# GTU-2-V1_1-20160516.net
KiCad netlist of a schematic drawn in Altium Designer
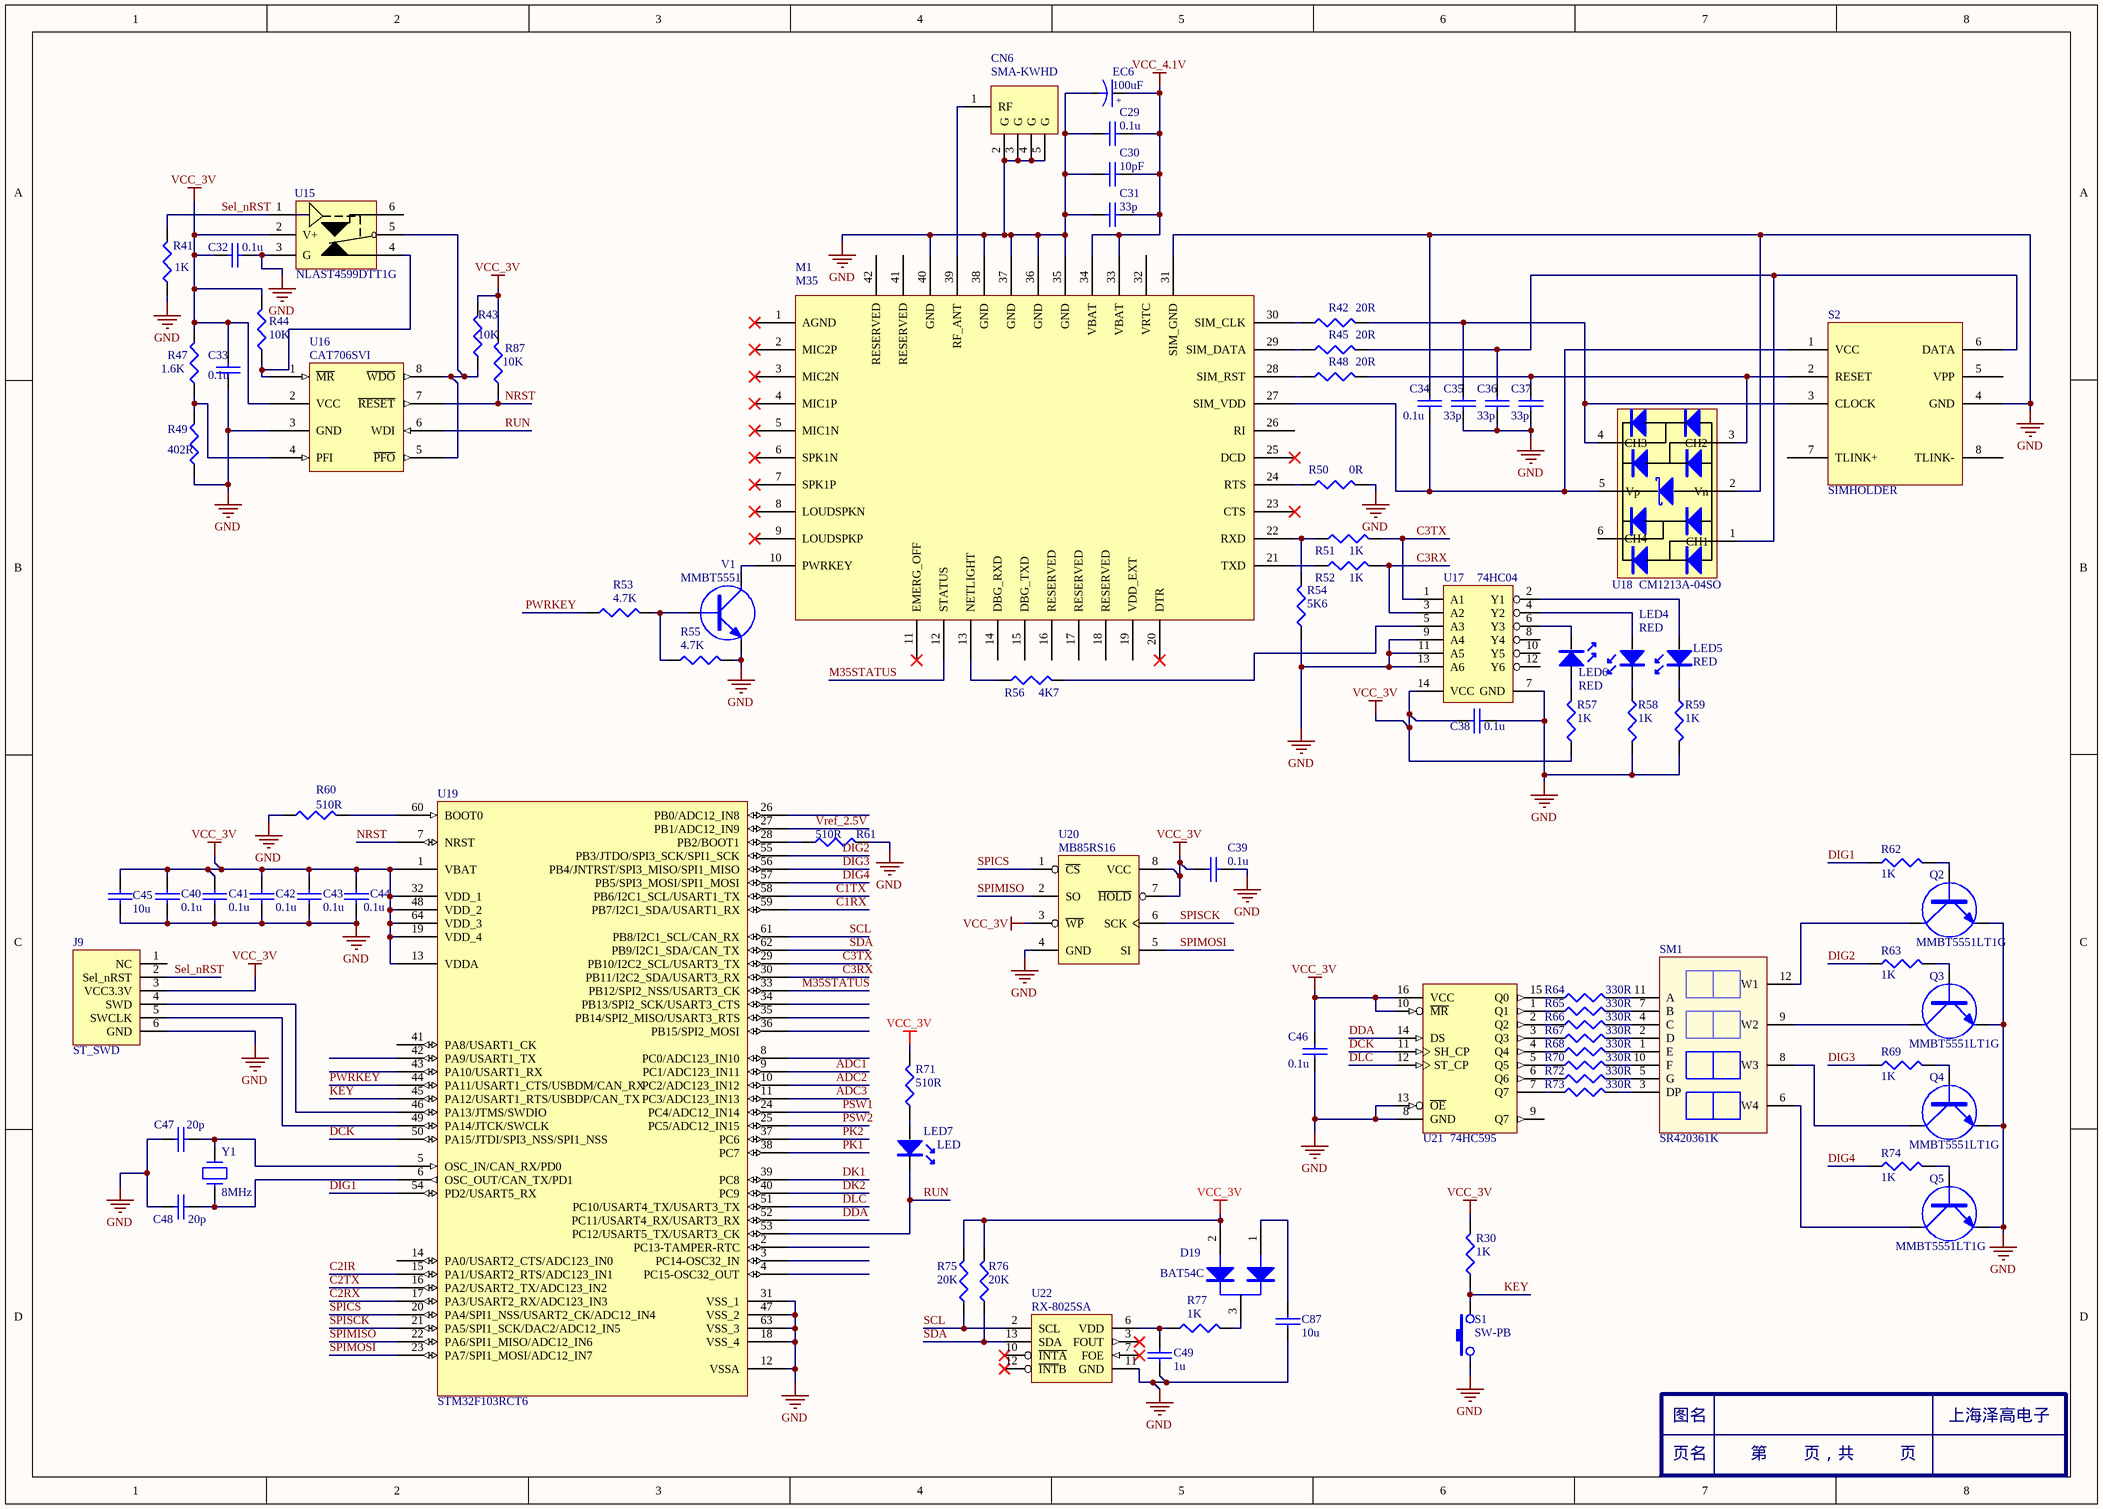
[diagram p0: GTU-2-V1.1-20160516.SCHDOC]

(export (version "E")
  (design (tool "Eeschema 10.0.6"))
  (components
    (comp (ref "4") (value "Component_1") (libsource (lib "*") (part "Component_1")))
    (comp (ref "C29")
      (value "0.1u")
      (footprint "0805-C")
      (description "Capacitor")
      (libsource (lib "STSCH-2014-01-20    ") (part "CAP"))
    )
    (comp (ref "C30")
      (value "10pF")
      (footprint "0805-C")
      (description "Capacitor")
      (libsource (lib "STSCH-2014-01-20    ") (part "CAP"))
    )
    (comp (ref "C31")
      (value "33p")
      (footprint "0805-C")
      (description "Capacitor")
      (libsource (lib "STSCH-2014-01-20    ") (part "CAP"))
    )
    (comp (ref "C32")
      (value "0.1u")
      (footprint "0805-C")
      (description "Capacitor")
      (fields (field (name "MFG") "TDK"))
      (libsource (lib "SCHLIB-ZG-2015.12.11      ") (part "CAP"))
    )
    (comp (ref "C33")
      (value "0.1u")
      (footprint "0805-C")
      (description "Capacitor")
      (libsource (lib "STSCH-2011-12-16") (part "CAP"))
    )
    (comp (ref "C34")
      (value "0.1u")
      (footprint "0805-C")
      (description "Capacitor")
      (libsource (lib "STSCH-2014-01-20    ") (part "CAP"))
    )
    (comp (ref "C35")
      (value "33p")
      (footprint "0805-C")
      (description "Capacitor")
      (libsource (lib "STSCH-2014-01-20    ") (part "CAP"))
    )
    (comp (ref "C36")
      (value "33p")
      (footprint "0805-C")
      (description "Capacitor")
      (libsource (lib "STSCH-2014-01-20    ") (part "CAP"))
    )
    (comp (ref "C37")
      (value "33p")
      (footprint "0805-C")
      (description "Capacitor")
      (libsource (lib "STSCH-2014-01-20    ") (part "CAP"))
    )
    (comp (ref "C38")
      (value "0.1u")
      (footprint "0805-C")
      (description "Capacitor")
      (libsource (lib "STSCH-2013-02-22   ") (part "CAP"))
    )
    (comp (ref "C39")
      (value "0.1u")
      (footprint "0805-C")
      (description "Capacitor")
      (libsource (lib "STSCH-2013-02-22   ") (part "CAP"))
    )
    (comp (ref "C40")
      (value "0.1u")
      (footprint "0805-C")
      (description "Capacitor")
      (libsource (lib "*") (part "CAP"))
    )
    (comp (ref "C41")
      (value "0.1u")
      (footprint "0805-C")
      (description "Capacitor")
      (libsource (lib "*") (part "CAP"))
    )
    (comp (ref "C42")
      (value "0.1u")
      (footprint "0805-C")
      (description "Capacitor")
      (libsource (lib "*") (part "CAP"))
    )
    (comp (ref "C43")
      (value "0.1u")
      (footprint "0805-C")
      (description "Capacitor")
      (libsource (lib "*") (part "CAP"))
    )
    (comp (ref "C44")
      (value "0.1u")
      (footprint "0805-C")
      (description "Capacitor")
      (libsource (lib "*") (part "CAP"))
    )
    (comp (ref "C45")
      (value "10u")
      (footprint "0805-C")
      (description "Capacitor")
      (libsource (lib "*") (part "CAP"))
    )
    (comp (ref "C46")
      (value "0.1u")
      (footprint "0805-C")
      (description "Capacitor")
      (libsource (lib "STSCH-2013-02-22   ") (part "CAP"))
    )
    (comp (ref "C47")
      (value "20p")
      (footprint "0805-C")
      (description "Capacitor")
      (libsource (lib "*") (part "CAP"))
    )
    (comp (ref "C48")
      (value "20p")
      (footprint "0805-C")
      (description "Capacitor")
      (libsource (lib "*") (part "CAP"))
    )
    (comp (ref "C49")
      (value "1u")
      (footprint "0805-C")
      (description "Capacitor")
      (libsource (lib "") (part "CAP_1"))
    )
    (comp (ref "C87")
      (value "10u")
      (footprint "0805-C")
      (description "Capacitor")
      (libsource (lib "") (part "CAP_1"))
    )
    (comp (ref "CN6")
      (value "SMA-KWHD")
      (footprint "SMA-KWHD")
      (description "RF插座")
      (libsource (lib "STSCH-2014-02-13    ") (part "SMA-KWHD"))
    )
    (comp (ref "D19") (value "BAT54C") (footprint "BAT54S/SOT-23") (libsource (lib "*") (part "BAT54C")))
    (comp (ref "EC6")
      (value "100uF")
      (footprint "7361-V")
      (libsource (lib "STSCH-2014-01-20    ") (part "CAP Tan"))
    )
    (comp (ref "J9")
      (value "ST_SWD")
      (footprint "SWD_DOWNLOAD")
      (description "STM32 SWD调试端口")
      (libsource (lib "SCHLIB-ZG-2015.12.11      ") (part "ST_SWD"))
    )
    (comp (ref "LED4")
      (value "RED")
      (footprint "0805-LED")
      (libsource (lib "STSCH-2012-11-26   ") (part "LED"))
    )
    (comp (ref "LED5")
      (value "RED")
      (footprint "0805-LED")
      (libsource (lib "STSCH-2012-11-26   ") (part "LED"))
    )
    (comp (ref "LED6")
      (value "RED")
      (footprint "0805-LED")
      (libsource (lib "STSCH-2012-11-26   ") (part "LED"))
    )
    (comp (ref "LED7") (value "LED") (footprint "0805-LED") (libsource (lib "STSCH-20110618") (part "LED")))
    (comp (ref "M1") (value "M35") (footprint "M35") (libsource (lib "STSCH-2014-01-20    ") (part "M35")))
    (comp (ref "Q2")
      (value "MMBT5551")
      (footprint "SOT-23")
      (description "NPN Transistor 160V 0.6A")
      (fields (field (name "MFG") "DIODES") (field (name "MFG2-PN") "MMBT5551LT1G"))
      (libsource (lib "SCHLIB-ZG-2016.01.18      ") (part "MMBT5551"))
    )
    (comp (ref "Q3")
      (value "MMBT5551")
      (footprint "SOT-23")
      (description "NPN Transistor 160V 0.6A")
      (fields (field (name "MFG") "DIODES") (field (name "MFG2-PN") "MMBT5551LT1G"))
      (libsource (lib "SCHLIB-ZG-2016.01.18      ") (part "MMBT5551"))
    )
    (comp (ref "Q4")
      (value "MMBT5551")
      (footprint "SOT-23")
      (description "NPN Transistor 160V 0.6A")
      (fields (field (name "MFG") "DIODES") (field (name "MFG2-PN") "MMBT5551LT1G"))
      (libsource (lib "SCHLIB-ZG-2016.01.18      ") (part "MMBT5551"))
    )
    (comp (ref "Q5")
      (value "MMBT5551")
      (footprint "SOT-23")
      (description "NPN Transistor 160V 0.6A")
      (fields (field (name "MFG") "DIODES") (field (name "MFG2-PN") "MMBT5551LT1G"))
      (libsource (lib "SCHLIB-ZG-2016.01.18      ") (part "MMBT5551"))
    )
    (comp (ref "R30") (value "1K") (footprint "0805-R") (libsource (lib "STSCH-2014-03-27    ") (part "RES")))
    (comp (ref "R41")
      (value "1K")
      (footprint "0805-R")
      (description "电阻")
      (fields (field (name "MFG") "YAGO") (field (name "Comment") "RES"))
      (libsource (lib "SCHLIB-ZG-2015.12.11      ") (part "RES"))
    )
    (comp (ref "R42")
      (value "20R")
      (footprint "0805-R")
      (libsource (lib "STSCH-2014-01-20    ") (part "RES"))
    )
    (comp (ref "R43") (value "10K") (footprint "0805-R") (libsource (lib "*") (part "RES")))
    (comp (ref "R44") (value "10K") (footprint "0805-R") (libsource (lib "*") (part "RES")))
    (comp (ref "R45")
      (value "20R")
      (footprint "0805-R")
      (libsource (lib "STSCH-2014-01-20    ") (part "RES"))
    )
    (comp (ref "R47")
      (value "1.6K")
      (footprint "0805-R")
      (description "电阻")
      (fields (field (name "MFG") "YAGO"))
      (libsource (lib "SCHLIB-ZG-2015.12.11      ") (part "RES"))
    )
    (comp (ref "R48")
      (value "20R")
      (footprint "0805-R")
      (libsource (lib "STSCH-2014-01-20    ") (part "RES"))
    )
    (comp (ref "R49")
      (value "402R")
      (footprint "0805-R")
      (description "电阻")
      (fields (field (name "MFG") "YAGO"))
      (libsource (lib "SCHLIB-ZG-2015.12.11      ") (part "RES"))
    )
    (comp (ref "R50") (value "0R") (footprint "0805-R") (libsource (lib "STSCH-2014-01-20    ") (part "RES")))
    (comp (ref "R51") (value "1K") (footprint "0805-R") (libsource (lib "STSCH-2014-01-20    ") (part "RES")))
    (comp (ref "R52") (value "1K") (footprint "0805-R") (libsource (lib "STSCH-2014-01-20    ") (part "RES")))
    (comp (ref "R53")
      (value "4.7K")
      (footprint "0805-R")
      (libsource (lib "STSCH-2014-01-20    ") (part "RES"))
    )
    (comp (ref "R54")
      (value "5K6")
      (footprint "0805-R")
      (libsource (lib "STSCH-2014-01-20    ") (part "RES"))
    )
    (comp (ref "R55")
      (value "4.7K")
      (footprint "0805-R")
      (libsource (lib "STSCH-2014-01-20    ") (part "RES"))
    )
    (comp (ref "R56")
      (value "4K7")
      (footprint "0805-R")
      (libsource (lib "STSCH-2014-02-12    ") (part "RES"))
    )
    (comp (ref "R57") (value "1K") (footprint "0805-R") (libsource (lib "STSCH-2012-11-26   ") (part "RES")))
    (comp (ref "R58") (value "1K") (footprint "0805-R") (libsource (lib "STSCH-2012-11-26   ") (part "RES")))
    (comp (ref "R59") (value "1K") (footprint "0805-R") (libsource (lib "STSCH-2012-11-26   ") (part "RES")))
    (comp (ref "R60") (value "510R") (footprint "0805-R") (libsource (lib "*") (part "RES")))
    (comp (ref "R61") (value "510R") (footprint "0805-R") (libsource (lib "*") (part "RES")))
    (comp (ref "R62")
      (value "1K")
      (footprint "0805-R")
      (description "电阻")
      (fields (field (name "MFG") "YAGO") (field (name "Comment") "RES"))
      (libsource (lib "SCHLIB-ZG-2016.01.18      ") (part "RES"))
    )
    (comp (ref "R63")
      (value "1K")
      (footprint "0805-R")
      (description "电阻")
      (fields (field (name "MFG") "YAGO") (field (name "Comment") "RES"))
      (libsource (lib "SCHLIB-ZG-2016.01.18      ") (part "RES"))
    )
    (comp (ref "R64") (value "330R") (footprint "0805-R") (libsource (lib "") (part "RES_1")))
    (comp (ref "R65") (value "330R") (footprint "0805-R") (libsource (lib "") (part "RES_1")))
    (comp (ref "R66") (value "330R") (footprint "0805-R") (libsource (lib "") (part "RES_1")))
    (comp (ref "R67") (value "330R") (footprint "0805-R") (libsource (lib "") (part "RES_1")))
    (comp (ref "R68") (value "330R") (footprint "0805-R") (libsource (lib "") (part "RES_1")))
    (comp (ref "R69")
      (value "1K")
      (footprint "0805-R")
      (description "电阻")
      (fields (field (name "MFG") "YAGO") (field (name "Comment") "RES"))
      (libsource (lib "SCHLIB-ZG-2016.01.18      ") (part "RES"))
    )
    (comp (ref "R70") (value "330R") (footprint "0805-R") (libsource (lib "") (part "RES_1")))
    (comp (ref "R71") (value "510R") (footprint "0805-R") (libsource (lib "STSCH-20110618") (part "RES")))
    (comp (ref "R72") (value "330R") (footprint "0805-R") (libsource (lib "") (part "RES_1")))
    (comp (ref "R73") (value "330R") (footprint "0805-R") (libsource (lib "") (part "RES_1")))
    (comp (ref "R74")
      (value "1K")
      (footprint "0805-R")
      (description "电阻")
      (fields (field (name "MFG") "YAGO") (field (name "Comment") "RES"))
      (libsource (lib "SCHLIB-ZG-2016.01.18      ") (part "RES"))
    )
    (comp (ref "R75") (value "20K") (footprint "0805-R") (libsource (lib "") (part "RES_1")))
    (comp (ref "R76") (value "20K") (footprint "0805-R") (libsource (lib "") (part "RES_1")))
    (comp (ref "R77") (value "1K") (footprint "0805-R") (libsource (lib "STSCH-2013-08-08    ") (part "RES")))
    (comp (ref "R87") (value "10K") (footprint "0805-R") (libsource (lib "*") (part "RES")))
    (comp (ref "S1")
      (value "SW-PB")
      (footprint "JMP")
      (description "轻触按钮")
      (libsource (lib "STSCH-2014-03-27    ") (part "SW-PB"))
    )
    (comp (ref "S2")
      (value "SIMHOLDER")
      (footprint "SIM-HOLDER")
      (libsource (lib "STSCH-2014-01-20    ") (part "SIMHOLDER"))
    )
    (comp (ref "SM1")
      (value "SR420361K")
      (footprint "SR420361")
      (description "共阴极0.28寸4位数码管品牌ARK")
      (libsource (lib "SCHLIB-ZG-2016.01.18      ") (part "SR420361"))
    )
    (comp (ref "U15")
      (value "NLAST4599DTT1G")
      (footprint "SOT-23-6")
      (libsource (lib "轨旁检测-20151210") (part "NLAST4599DTT1G"))
    )
    (comp (ref "U16") (value "CAT706SVI") (footprint "SO-8") (libsource (lib "*") (part "SP706T")))
    (comp (ref "U17")
      (value "74HC04")
      (footprint "SO-14")
      (libsource (lib "STSCH-2014-05-18     ") (part "74HC04"))
    )
    (comp (ref "U18")
      (value "CM1213A-04SO")
      (footprint "SOT-23-6")
      (libsource (lib "STSCH-2015.09.30  ") (part "CM1213A-04SO"))
    )
    (comp (ref "U19")
      (value "STM32F103RCT6")
      (footprint "LQFP-64")
      (libsource (lib "STSCH-2014-01-15") (part "STM32F103RCT6"))
    )
    (comp (ref "U20")
      (value "MB85RS16")
      (footprint "SO-8")
      (libsource (lib "STSCH-2013-02-22   ") (part "FM25256B"))
    )
    (comp (ref "U21")
      (value "74HC595")
      (footprint "SO-16")
      (description "8位移位寄存器")
      (fields (field (name "MFG") "NXP"))
      (libsource (lib "SCHLIB-ZG-2016.01.18      ") (part "74HC595"))
    )
    (comp (ref "U22") (value "RX-8025SA") (footprint "SO-14") (libsource (lib "*") (part "RX-8025SA")))
    (comp (ref "V1")
      (value "MMBT5551")
      (footprint "SOT-23")
      (description "贴片NPN")
      (libsource (lib "STSCH-2014-01-20    ") (part "MMBT5551"))
    )
    (comp (ref "Y1")
      (value "8MHz")
      (footprint "SM-49")
      (description "Crystal")
      (libsource (lib "*") (part "CRYSTAL"))
    )
  )
  (nets
    (net (code "1") (name "/ADC1") (class "Default")
      (node (ref "U19") (pin "9") (pinfunction "PC1/ADC123_IN11_9") (pintype "bidirectional"))
    )
    (net (code "2") (name "/ADC2") (class "Default")
      (node (ref "U19") (pin "10") (pinfunction "PC2/ADC123_IN12_10") (pintype "bidirectional"))
    )
    (net (code "3") (name "/ADC3") (class "Default")
      (node (ref "U19") (pin "11") (pinfunction "PC3/ADC123_IN13_11") (pintype "bidirectional"))
    )
    (net (code "4") (name "/C1RX") (class "Default")
      (node (ref "U19") (pin "59") (pinfunction "PB7/I2C1_SDA/USART1_RX_59") (pintype "bidirectional"))
    )
    (net (code "5") (name "/C1TX") (class "Default")
      (node (ref "U19") (pin "58") (pinfunction "PB6/I2C1_SCL/USART1_TX_58") (pintype "bidirectional"))
    )
    (net (code "6") (name "/C2IR") (class "Default")
      (node (ref "U19") (pin "15") (pinfunction "PA1/USART2_RTS/ADC123_IN1_15") (pintype "bidirectional"))
    )
    (net (code "7") (name "/C2RX") (class "Default")
      (node (ref "U19") (pin "17") (pinfunction "PA3/USART2_RX/ADC123_IN3_17") (pintype "bidirectional"))
    )
    (net (code "8") (name "/C2TX") (class "Default")
      (node (ref "U19") (pin "16") (pinfunction "PA2/USART2_TX/ADC123_IN2_16") (pintype "bidirectional"))
    )
    (net (code "9") (name "/C3RX") (class "Default")
      (node (ref "R52") (pin "2") (pinfunction "2_2") (pintype "passive"))
      (node (ref "U17") (pin "3") (pinfunction "A2_3") (pintype "passive"))
      (node (ref "U19") (pin "30") (pinfunction "PB11/I2C2_SDA/USART3_RX_30") (pintype "bidirectional"))
    )
    (net (code "10") (name "/C3TX") (class "Default")
      (node (ref "R51") (pin "2") (pinfunction "2_2") (pintype "passive"))
      (node (ref "U17") (pin "1") (pinfunction "A1_1") (pintype "passive"))
      (node (ref "U19") (pin "29") (pinfunction "PB10/I2C2_SCL/USART3_TX_29") (pintype "bidirectional"))
    )
    (net (code "11") (name "/DCK") (class "Default")
      (node (ref "U19") (pin "50") (pinfunction "PA15/JTDI/SPI3_NSS/SPI1_NSS_50") (pintype "bidirectional"))
      (node (ref "U21") (pin "11") (pinfunction "SH_CP_11") (pintype "input"))
    )
    (net (code "12") (name "/DDA") (class "Default")
      (node (ref "U19") (pin "52") (pinfunction "PC11/USART4_RX/USART3_RX_52") (pintype "bidirectional"))
      (node (ref "U21") (pin "14") (pinfunction "DS_14") (pintype "input"))
    )
    (net (code "13") (name "/DIG1") (class "Default")
      (node (ref "R62") (pin "1") (pinfunction "1_1") (pintype "passive"))
      (node (ref "U19") (pin "54") (pinfunction "PD2/USART5_RX_54") (pintype "bidirectional"))
    )
    (net (code "14") (name "/DIG2") (class "Default")
      (node (ref "R63") (pin "1") (pinfunction "1_1") (pintype "passive"))
      (node (ref "U19") (pin "55") (pinfunction "PB3/JTDO/SPI3_SCK/SPI1_SCK_55") (pintype "bidirectional"))
    )
    (net (code "15") (name "/DIG3") (class "Default")
      (node (ref "R69") (pin "1") (pinfunction "1_1") (pintype "passive"))
      (node (ref "U19") (pin "56") (pinfunction "PB4/JNTRST/SPI3_MISO/SPI1_MISO_56") (pintype "bidirectional"))
    )
    (net (code "16") (name "/DIG4") (class "Default")
      (node (ref "R74") (pin "1") (pinfunction "1_1") (pintype "passive"))
      (node (ref "U19") (pin "57") (pinfunction "PB5/SPI3_MOSI/SPI1_MOSI_57") (pintype "bidirectional"))
    )
    (net (code "17") (name "/DK1") (class "Default")
      (node (ref "U19") (pin "39") (pinfunction "PC8_39") (pintype "bidirectional"))
    )
    (net (code "18") (name "/DK2") (class "Default")
      (node (ref "U19") (pin "40") (pinfunction "PC9_40") (pintype "bidirectional"))
    )
    (net (code "19") (name "/DLC") (class "Default")
      (node (ref "U19") (pin "51") (pinfunction "PC10/USART4_TX/USART3_TX_51") (pintype "bidirectional"))
      (node (ref "U21") (pin "12") (pinfunction "ST_CP_12") (pintype "input"))
    )
    (net (code "20") (name "/KEY") (class "Default")
      (node (ref "R30") (pin "1") (pinfunction "1_1") (pintype "passive"))
      (node (ref "S1") (pin "2") (pinfunction "2_2") (pintype "passive"))
      (node (ref "U19") (pin "45") (pinfunction "PA12/USART1_RTS/USBDP/CAN_TX_45") (pintype "bidirectional"))
    )
    (net (code "21") (name "/M35STATUS") (class "Default")
      (node (ref "M1") (pin "12") (pinfunction "STATUS_12") (pintype "passive"))
      (node (ref "U19") (pin "33") (pinfunction "PB12/SPI2_NSS/USART3_CK_33") (pintype "bidirectional"))
    )
    (net (code "22") (name "/NRST") (class "Default")
      (node (ref "R87") (pin "1") (pinfunction "1_1") (pintype "passive"))
      (node (ref "U16") (pin "7") (pinfunction "~{RESET}_7") (pintype "output"))
      (node (ref "U19") (pin "7") (pinfunction "NRST_7") (pintype "bidirectional"))
    )
    (net (code "23") (name "/PK1") (class "Default")
      (node (ref "U19") (pin "38") (pinfunction "PC7_38") (pintype "bidirectional"))
    )
    (net (code "24") (name "/PK2") (class "Default")
      (node (ref "U19") (pin "37") (pinfunction "PC6_37") (pintype "bidirectional"))
    )
    (net (code "25") (name "/PSW1") (class "Default")
      (node (ref "U19") (pin "24") (pinfunction "PC4/ADC12_IN14_24") (pintype "bidirectional"))
    )
    (net (code "26") (name "/PSW2") (class "Default")
      (node (ref "U19") (pin "25") (pinfunction "PC5/ADC12_IN15_25") (pintype "bidirectional"))
    )
    (net (code "27") (name "/PWRKEY") (class "Default")
      (node (ref "R53") (pin "1") (pinfunction "1_1") (pintype "passive"))
      (node (ref "U19") (pin "44") (pinfunction "PA11/USART1_CTS/USBDM/CAN_RX_44") (pintype "bidirectional"))
    )
    (net (code "28") (name "/RUN") (class "Default")
      (node (ref "LED7") (pin "2") (pintype "passive"))
      (node (ref "U16") (pin "6") (pinfunction "WDI_6") (pintype "input"))
      (node (ref "U19") (pin "53") (pinfunction "PC12/USART5_TX/USART3_CK_53") (pintype "bidirectional"))
    )
    (net (code "29") (name "/SCL") (class "Default")
      (node (ref "R75") (pin "1") (pinfunction "1_1") (pintype "passive"))
      (node (ref "U19") (pin "61") (pinfunction "PB8/I2C1_SCL/CAN_RX_61") (pintype "bidirectional"))
      (node (ref "U22") (pin "2") (pinfunction "SCL_2") (pintype "open_collector"))
    )
    (net (code "30") (name "/SDA") (class "Default")
      (node (ref "R76") (pin "1") (pinfunction "1_1") (pintype "passive"))
      (node (ref "U19") (pin "62") (pinfunction "PB9/I2C1_SDA/CAN_TX_62") (pintype "bidirectional"))
      (node (ref "U22") (pin "13") (pinfunction "SDA_13") (pintype "passive"))
    )
    (net (code "31") (name "/SPICS") (class "Default")
      (node (ref "U19") (pin "20") (pinfunction "PA4/SPI1_NSS/USART2_CK/ADC12_IN4_20") (pintype "bidirectional"))
      (node (ref "U20") (pin "1") (pinfunction "~{CS}_1") (pintype "passive"))
    )
    (net (code "32") (name "/SPIMISO") (class "Default")
      (node (ref "U19") (pin "22") (pinfunction "PA6/SPI1_MISO/ADC12_IN6_22") (pintype "bidirectional"))
      (node (ref "U20") (pin "2") (pinfunction "SO_2") (pintype "passive"))
    )
    (net (code "33") (name "/SPIMOSI") (class "Default")
      (node (ref "U19") (pin "23") (pinfunction "PA7/SPI1_MOSI/ADC12_IN7_23") (pintype "bidirectional"))
      (node (ref "U20") (pin "5") (pinfunction "SI_5") (pintype "passive"))
    )
    (net (code "34") (name "/SPISCK") (class "Default")
      (node (ref "U19") (pin "21") (pinfunction "PA5/SPI1_SCK/DAC2/ADC12_IN5_21") (pintype "bidirectional"))
      (node (ref "U20") (pin "6") (pinfunction "SCK_6") (pintype "passive"))
    )
    (net (code "35") (name "/Sel_nRST") (class "Default")
      (node (ref "J9") (pin "2") (pinfunction "Sel_nRST_2") (pintype "passive"))
      (node (ref "R41") (pin "2") (pinfunction "2_2") (pintype "passive"))
      (node (ref "U15") (pin "1") (pinfunction "SELECT_1") (pintype "passive"))
    )
    (net (code "36") (name "/Vref_2.5V") (class "Default")
      (node (ref "U19") (pin "27") (pinfunction "PB1/ADC12_IN9_27") (pintype "bidirectional"))
    )
    (net (code "37") (name "GND") (class "Default")
      (node (ref "C29") (pin "2") (pinfunction "2_2") (pintype "passive"))
      (node (ref "C30") (pin "2") (pinfunction "2_2") (pintype "passive"))
      (node (ref "C31") (pin "2") (pinfunction "2_2") (pintype "passive"))
      (node (ref "C32") (pin "2") (pinfunction "2_2") (pintype "passive"))
      (node (ref "C33") (pin "2") (pinfunction "2_2") (pintype "passive"))
      (node (ref "C34") (pin "1") (pinfunction "1_1") (pintype "passive"))
      (node (ref "C35") (pin "2") (pinfunction "2_2") (pintype "passive"))
      (node (ref "C36") (pin "2") (pinfunction "2_2") (pintype "passive"))
      (node (ref "C37") (pin "2") (pinfunction "2_2") (pintype "passive"))
      (node (ref "C38") (pin "2") (pinfunction "2_2") (pintype "passive"))
      (node (ref "C39") (pin "2") (pinfunction "2_2") (pintype "passive"))
      (node (ref "C40") (pin "2") (pinfunction "2_2") (pintype "passive"))
      (node (ref "C41") (pin "2") (pinfunction "2_2") (pintype "passive"))
      (node (ref "C42") (pin "2") (pinfunction "2_2") (pintype "passive"))
      (node (ref "C43") (pin "2") (pinfunction "2_2") (pintype "passive"))
      (node (ref "C44") (pin "2") (pinfunction "2_2") (pintype "passive"))
      (node (ref "C45") (pin "2") (pinfunction "2_2") (pintype "passive"))
      (node (ref "C46") (pin "2") (pinfunction "2_2") (pintype "passive"))
      (node (ref "C47") (pin "2") (pinfunction "2_2") (pintype "passive"))
      (node (ref "C48") (pin "2") (pinfunction "2_2") (pintype "passive"))
      (node (ref "C49") (pin "2") (pinfunction "2_2") (pintype "passive"))
      (node (ref "C87") (pin "2") (pinfunction "2_2") (pintype "passive"))
      (node (ref "CN6") (pin "2") (pinfunction "G_2") (pintype "passive"))
      (node (ref "CN6") (pin "3") (pinfunction "G_3") (pintype "passive"))
      (node (ref "CN6") (pin "4") (pinfunction "G_4") (pintype "passive"))
      (node (ref "CN6") (pin "5") (pinfunction "G_5") (pintype "passive"))
      (node (ref "EC6") (pin "2") (pinfunction "2_2") (pintype "passive"))
      (node (ref "J9") (pin "6") (pinfunction "GND_6") (pintype "passive"))
      (node (ref "M1") (pin "31") (pinfunction "SIM_GND_31") (pintype "passive"))
      (node (ref "M1") (pin "35") (pinfunction "GND_35") (pintype "passive"))
      (node (ref "M1") (pin "36") (pinfunction "GND_36") (pintype "passive"))
      (node (ref "M1") (pin "37") (pinfunction "GND_37") (pintype "passive"))
      (node (ref "M1") (pin "38") (pinfunction "GND_38") (pintype "passive"))
      (node (ref "M1") (pin "40") (pinfunction "GND_40") (pintype "passive"))
      (node (ref "Q2") (pin "2") (pinfunction "E_2") (pintype "passive"))
      (node (ref "Q3") (pin "2") (pinfunction "E_2") (pintype "passive"))
      (node (ref "Q4") (pin "2") (pinfunction "E_2") (pintype "passive"))
      (node (ref "Q5") (pin "2") (pinfunction "E_2") (pintype "passive"))
      (node (ref "R41") (pin "1") (pinfunction "1_1") (pintype "passive"))
      (node (ref "R49") (pin "1") (pinfunction "1_1") (pintype "passive"))
      (node (ref "R50") (pin "2") (pinfunction "2_2") (pintype "passive"))
      (node (ref "R54") (pin "1") (pinfunction "1_1") (pintype "passive"))
      (node (ref "R55") (pin "2") (pinfunction "2_2") (pintype "passive"))
      (node (ref "R58") (pin "2") (pinfunction "2_2") (pintype "passive"))
      (node (ref "R59") (pin "2") (pinfunction "2_2") (pintype "passive"))
      (node (ref "R60") (pin "1") (pinfunction "1_1") (pintype "passive"))
      (node (ref "R61") (pin "2") (pinfunction "2_2") (pintype "passive"))
      (node (ref "S1") (pin "1") (pinfunction "1_1") (pintype "passive"))
      (node (ref "S2") (pin "4") (pinfunction "GND_4") (pintype "passive"))
      (node (ref "U15") (pin "3") (pinfunction "G_3") (pintype "passive"))
      (node (ref "U16") (pin "3") (pinfunction "GND_3") (pintype "power_in"))
      (node (ref "U17") (pin "11") (pinfunction "A5_11") (pintype "passive"))
      (node (ref "U17") (pin "13") (pinfunction "A6_13") (pintype "passive"))
      (node (ref "U17") (pin "7") (pinfunction "GND_7") (pintype "passive"))
      (node (ref "U17") (pin "9") (pinfunction "A4_9") (pintype "passive"))
      (node (ref "U18") (pin "2") (pinfunction "Vn_2") (pintype "passive"))
      (node (ref "U19") (pin "12") (pinfunction "VSSA_12") (pintype "power_in"))
      (node (ref "U19") (pin "18") (pinfunction "VSS_4_18") (pintype "power_in"))
      (node (ref "U19") (pin "31") (pinfunction "VSS_1_31") (pintype "power_in"))
      (node (ref "U19") (pin "47") (pinfunction "VSS_2_47") (pintype "power_in"))
      (node (ref "U19") (pin "63") (pinfunction "VSS_3_63") (pintype "power_in"))
      (node (ref "U20") (pin "4") (pinfunction "GND_4") (pintype "passive"))
      (node (ref "U21") (pin "13") (pinfunction "~{OE}_13") (pintype "input"))
      (node (ref "U21") (pin "8") (pinfunction "GND_8") (pintype "power_in"))
      (node (ref "U22") (pin "11") (pinfunction "GND_11") (pintype "power_in"))
      (node (ref "V1") (pin "2") (pinfunction "E_2") (pintype "passive"))
    )
    (net (code "38") (name "Net-(C87-Pad1)") (class "Default")
      (node (ref "C87") (pin "1") (pinfunction "1_1") (pintype "passive"))
      (node (ref "D19") (pin "1") (pintype "passive"))
    )
    (net (code "39") (name "Net-(CN6-RF)") (class "Default")
      (node (ref "CN6") (pin "1") (pinfunction "RF_1") (pintype "passive"))
      (node (ref "M1") (pin "39") (pinfunction "RF_ANT_39") (pintype "passive"))
    )
    (net (code "40") (name "Net-(D19-Pad3)") (class "Default")
      (node (ref "D19") (pin "3") (pintype "passive"))
      (node (ref "R77") (pin "2") (pinfunction "2_2") (pintype "passive"))
    )
    (net (code "41") (name "Net-(J9-SWCLK)") (class "Default")
      (node (ref "J9") (pin "5") (pinfunction "SWCLK_5") (pintype "passive"))
      (node (ref "U19") (pin "49") (pinfunction "PA14/JTCK/SWCLK_49") (pintype "bidirectional"))
    )
    (net (code "42") (name "Net-(J9-SWD)") (class "Default")
      (node (ref "J9") (pin "4") (pinfunction "SWD_4") (pintype "passive"))
      (node (ref "U19") (pin "46") (pinfunction "PA13/JTMS/SWDIO_46") (pintype "bidirectional"))
    )
    (net (code "43") (name "Net-(LED4-Pad2)") (class "Default")
      (node (ref "LED4") (pin "2") (pintype "passive"))
      (node (ref "R58") (pin "1") (pinfunction "1_1") (pintype "passive"))
    )
    (net (code "44") (name "Net-(LED5-Pad2)") (class "Default")
      (node (ref "LED5") (pin "2") (pintype "passive"))
      (node (ref "R59") (pin "1") (pinfunction "1_1") (pintype "passive"))
    )
    (net (code "45") (name "Net-(LED6-Pad1)") (class "Default")
      (node (ref "LED6") (pin "1") (pintype "passive"))
      (node (ref "R57") (pin "2") (pinfunction "2_2") (pintype "passive"))
    )
    (net (code "46") (name "Net-(LED7-Pad1)") (class "Default")
      (node (ref "LED7") (pin "1") (pintype "passive"))
      (node (ref "R71") (pin "1") (pinfunction "1_1") (pintype "passive"))
    )
    (net (code "47") (name "Net-(M1-NETLIGHT)") (class "Default")
      (node (ref "M1") (pin "13") (pinfunction "NETLIGHT_13") (pintype "passive"))
      (node (ref "R56") (pin "1") (pinfunction "1_1") (pintype "passive"))
    )
    (net (code "48") (name "Net-(M1-PWRKEY)") (class "Default")
      (node (ref "M1") (pin "10") (pinfunction "PWRKEY_10") (pintype "passive"))
      (node (ref "V1") (pin "3") (pinfunction "C_3") (pintype "passive"))
    )
    (net (code "49") (name "Net-(M1-RTS)") (class "Default")
      (node (ref "M1") (pin "24") (pinfunction "RTS_24") (pintype "passive"))
      (node (ref "R50") (pin "1") (pinfunction "1_1") (pintype "passive"))
    )
    (net (code "50") (name "Net-(M1-RXD)") (class "Default")
      (node (ref "M1") (pin "22") (pinfunction "RXD_22") (pintype "passive"))
      (node (ref "R51") (pin "1") (pinfunction "1_1") (pintype "passive"))
      (node (ref "R54") (pin "2") (pinfunction "2_2") (pintype "passive"))
    )
    (net (code "51") (name "Net-(M1-SIM_CLK)") (class "Default")
      (node (ref "M1") (pin "30") (pinfunction "SIM_CLK_30") (pintype "passive"))
      (node (ref "R42") (pin "1") (pinfunction "1_1") (pintype "passive"))
    )
    (net (code "52") (name "Net-(M1-SIM_DATA)") (class "Default")
      (node (ref "M1") (pin "29") (pinfunction "SIM_DATA_29") (pintype "passive"))
      (node (ref "R45") (pin "1") (pinfunction "1_1") (pintype "passive"))
    )
    (net (code "53") (name "Net-(M1-SIM_RST)") (class "Default")
      (node (ref "M1") (pin "28") (pinfunction "SIM_RST_28") (pintype "passive"))
      (node (ref "R48") (pin "1") (pinfunction "1_1") (pintype "passive"))
    )
    (net (code "54") (name "Net-(M1-SIM_VDD)") (class "Default")
      (node (ref "C34") (pin "2") (pinfunction "2_2") (pintype "passive"))
      (node (ref "M1") (pin "27") (pinfunction "SIM_VDD_27") (pintype "passive"))
      (node (ref "S2") (pin "1") (pinfunction "VCC_1") (pintype "passive"))
      (node (ref "U18") (pin "5") (pinfunction "Vp_5") (pintype "passive"))
    )
    (net (code "55") (name "Net-(M1-TXD)") (class "Default")
      (node (ref "M1") (pin "21") (pinfunction "TXD_21") (pintype "passive"))
      (node (ref "R52") (pin "1") (pinfunction "1_1") (pintype "passive"))
    )
    (net (code "56") (name "Net-(Q2-B)") (class "Default")
      (node (ref "Q2") (pin "1") (pinfunction "B_1") (pintype "passive"))
      (node (ref "R62") (pin "2") (pinfunction "2_2") (pintype "passive"))
    )
    (net (code "57") (name "Net-(Q2-C)") (class "Default")
      (node (ref "Q2") (pin "3") (pinfunction "C_3") (pintype "passive"))
      (node (ref "SM1") (pin "12") (pinfunction "W1_12") (pintype "passive"))
    )
    (net (code "58") (name "Net-(Q3-B)") (class "Default")
      (node (ref "Q3") (pin "1") (pinfunction "B_1") (pintype "passive"))
      (node (ref "R63") (pin "2") (pinfunction "2_2") (pintype "passive"))
    )
    (net (code "59") (name "Net-(Q3-C)") (class "Default")
      (node (ref "Q3") (pin "3") (pinfunction "C_3") (pintype "passive"))
      (node (ref "SM1") (pin "9") (pinfunction "W2_9") (pintype "passive"))
    )
    (net (code "60") (name "Net-(Q4-B)") (class "Default")
      (node (ref "Q4") (pin "1") (pinfunction "B_1") (pintype "passive"))
      (node (ref "R69") (pin "2") (pinfunction "2_2") (pintype "passive"))
    )
    (net (code "61") (name "Net-(Q4-C)") (class "Default")
      (node (ref "Q4") (pin "3") (pinfunction "C_3") (pintype "passive"))
      (node (ref "SM1") (pin "8") (pinfunction "W3_8") (pintype "passive"))
    )
    (net (code "62") (name "Net-(Q5-B)") (class "Default")
      (node (ref "Q5") (pin "1") (pinfunction "B_1") (pintype "passive"))
      (node (ref "R74") (pin "2") (pinfunction "2_2") (pintype "passive"))
    )
    (net (code "63") (name "Net-(Q5-C)") (class "Default")
      (node (ref "Q5") (pin "3") (pinfunction "C_3") (pintype "passive"))
      (node (ref "SM1") (pin "6") (pinfunction "W4_6") (pintype "passive"))
    )
    (net (code "64") (name "Net-(R73-Pad1)") (class "Default")
      (node (ref "R73") (pin "1") (pinfunction "1_1") (pintype "passive"))
      (node (ref "U21") (pin "7") (pinfunction "Q7_7") (pintype "tri_state"))
    )
    (net (code "65") (name "Net-(S2-CLOCK)") (class "Default")
      (node (ref "C35") (pin "1") (pinfunction "1_1") (pintype "passive"))
      (node (ref "R42") (pin "2") (pinfunction "2_2") (pintype "passive"))
      (node (ref "S2") (pin "3") (pinfunction "CLOCK_3") (pintype "passive"))
      (node (ref "U18") (pin "4") (pinfunction "CH3_4") (pintype "passive"))
    )
    (net (code "66") (name "Net-(S2-DATA)") (class "Default")
      (node (ref "C36") (pin "1") (pinfunction "1_1") (pintype "passive"))
      (node (ref "R45") (pin "2") (pinfunction "2_2") (pintype "passive"))
      (node (ref "S2") (pin "6") (pinfunction "DATA_6") (pintype "passive"))
      (node (ref "U18") (pin "1") (pinfunction "CH1_1") (pintype "passive"))
    )
    (net (code "67") (name "Net-(S2-RESET)") (class "Default")
      (node (ref "C37") (pin "1") (pinfunction "1_1") (pintype "passive"))
      (node (ref "R48") (pin "2") (pinfunction "2_2") (pintype "passive"))
      (node (ref "S2") (pin "2") (pinfunction "RESET_2") (pintype "passive"))
      (node (ref "U18") (pin "3") (pinfunction "CH2_3") (pintype "passive"))
    )
    (net (code "68") (name "Net-(SM1-A)") (class "Default")
      (node (ref "R64") (pin "2") (pinfunction "2_2") (pintype "passive"))
      (node (ref "SM1") (pin "11") (pinfunction "A_11") (pintype "passive"))
    )
    (net (code "69") (name "Net-(SM1-B)") (class "Default")
      (node (ref "R65") (pin "2") (pinfunction "2_2") (pintype "passive"))
      (node (ref "SM1") (pin "7") (pinfunction "B_7") (pintype "passive"))
    )
    (net (code "70") (name "Net-(SM1-C)") (class "Default")
      (node (ref "R66") (pin "2") (pinfunction "2_2") (pintype "passive"))
      (node (ref "SM1") (pin "4") (pinfunction "C_4") (pintype "passive"))
    )
    (net (code "71") (name "Net-(SM1-D)") (class "Default")
      (node (ref "R67") (pin "2") (pinfunction "2_2") (pintype "passive"))
      (node (ref "SM1") (pin "2") (pinfunction "D_2") (pintype "passive"))
    )
    (net (code "72") (name "Net-(SM1-DP)") (class "Default")
      (node (ref "R73") (pin "2") (pinfunction "2_2") (pintype "passive"))
      (node (ref "SM1") (pin "3") (pinfunction "DP_3") (pintype "passive"))
    )
    (net (code "73") (name "Net-(SM1-E)") (class "Default")
      (node (ref "R68") (pin "2") (pinfunction "2_2") (pintype "passive"))
      (node (ref "SM1") (pin "1") (pinfunction "E_1") (pintype "passive"))
    )
    (net (code "74") (name "Net-(SM1-F)") (class "Default")
      (node (ref "R70") (pin "2") (pinfunction "2_2") (pintype "passive"))
      (node (ref "SM1") (pin "10") (pinfunction "F_10") (pintype "passive"))
    )
    (net (code "75") (name "Net-(SM1-G)") (class "Default")
      (node (ref "R72") (pin "2") (pinfunction "2_2") (pintype "passive"))
      (node (ref "SM1") (pin "5") (pinfunction "G_5") (pintype "passive"))
    )
    (net (code "76") (name "Net-(U15-CON)") (class "Default")
      (node (ref "R43") (pin "1") (pinfunction "1_1") (pintype "passive"))
      (node (ref "U15") (pin "5") (pinfunction "CON_5") (pintype "passive"))
      (node (ref "U16") (pin "5") (pinfunction "~{PFO}_5") (pintype "output"))
      (node (ref "U16") (pin "8") (pinfunction "~{WDO}_8") (pintype "output"))
    )
    (net (code "77") (name "Net-(U15-NC)") (class "Default")
      (node (ref "R44") (pin "1") (pinfunction "1_1") (pintype "passive"))
      (node (ref "U15") (pin "4") (pinfunction "NC_4") (pintype "passive"))
      (node (ref "U16") (pin "1") (pinfunction "~{MR}_1") (pintype "input"))
    )
    (net (code "78") (name "Net-(U16-PFI)") (class "Default")
      (node (ref "R47") (pin "1") (pinfunction "1_1") (pintype "passive"))
      (node (ref "R49") (pin "2") (pinfunction "2_2") (pintype "passive"))
      (node (ref "U16") (pin "4") (pinfunction "PFI_4") (pintype "input"))
    )
    (net (code "79") (name "Net-(U17-A3)") (class "Default")
      (node (ref "R56") (pin "2") (pinfunction "2_2") (pintype "passive"))
      (node (ref "U17") (pin "5") (pinfunction "A3_5") (pintype "passive"))
    )
    (net (code "80") (name "Net-(U17-Y1)") (class "Default")
      (node (ref "LED5") (pin "1") (pintype "passive"))
      (node (ref "U17") (pin "2") (pinfunction "Y1_2") (pintype "passive"))
    )
    (net (code "81") (name "Net-(U17-Y2)") (class "Default")
      (node (ref "LED4") (pin "1") (pintype "passive"))
      (node (ref "U17") (pin "4") (pinfunction "Y2_4") (pintype "passive"))
    )
    (net (code "82") (name "Net-(U17-Y3)") (class "Default")
      (node (ref "LED6") (pin "2") (pintype "passive"))
      (node (ref "U17") (pin "6") (pinfunction "Y3_6") (pintype "passive"))
    )
    (net (code "83") (name "Net-(U19-BOOT0)") (class "Default")
      (node (ref "R60") (pin "2") (pinfunction "2_2") (pintype "passive"))
      (node (ref "U19") (pin "60") (pinfunction "BOOT0_60") (pintype "input"))
    )
    (net (code "84") (name "Net-(U19-OSC_IN{slash}CAN_RX{slash}PD0)") (class "Default")
      (node (ref "C47") (pin "1") (pinfunction "1_1") (pintype "passive"))
      (node (ref "U19") (pin "5") (pinfunction "OSC_IN/CAN_RX/PD0_5") (pintype "input"))
      (node (ref "Y1") (pin "2") (pinfunction "2_2") (pintype "passive"))
    )
    (net (code "85") (name "Net-(U19-OSC_OUT{slash}CAN_TX{slash}PD1)") (class "Default")
      (node (ref "C48") (pin "1") (pinfunction "1_1") (pintype "passive"))
      (node (ref "U19") (pin "6") (pinfunction "OSC_OUT/CAN_TX/PD1_6") (pintype "output"))
      (node (ref "Y1") (pin "1") (pinfunction "1_1") (pintype "passive"))
    )
    (net (code "86") (name "Net-(U19-PB2{slash}BOOT1)") (class "Default")
      (node (ref "R61") (pin "1") (pinfunction "1_1") (pintype "passive"))
      (node (ref "U19") (pin "28") (pinfunction "PB2/BOOT1_28") (pintype "bidirectional"))
    )
    (net (code "87") (name "Net-(U21-Q0)") (class "Default")
      (node (ref "R64") (pin "1") (pinfunction "1_1") (pintype "passive"))
      (node (ref "U21") (pin "15") (pinfunction "Q0_15") (pintype "output"))
    )
    (net (code "88") (name "Net-(U21-Q1)") (class "Default")
      (node (ref "R65") (pin "1") (pinfunction "1_1") (pintype "passive"))
      (node (ref "U21") (pin "1") (pinfunction "Q1_1") (pintype "output"))
    )
    (net (code "89") (name "Net-(U21-Q2)") (class "Default")
      (node (ref "R66") (pin "1") (pinfunction "1_1") (pintype "passive"))
      (node (ref "U21") (pin "2") (pinfunction "Q2_2") (pintype "output"))
    )
    (net (code "90") (name "Net-(U21-Q3)") (class "Default")
      (node (ref "R67") (pin "1") (pinfunction "1_1") (pintype "passive"))
      (node (ref "U21") (pin "3") (pinfunction "Q3_3") (pintype "output"))
    )
    (net (code "91") (name "Net-(U21-Q4)") (class "Default")
      (node (ref "R68") (pin "1") (pinfunction "1_1") (pintype "passive"))
      (node (ref "U21") (pin "4") (pinfunction "Q4_4") (pintype "output"))
    )
    (net (code "92") (name "Net-(U21-Q5)") (class "Default")
      (node (ref "R70") (pin "1") (pinfunction "1_1") (pintype "passive"))
      (node (ref "U21") (pin "5") (pinfunction "Q5_5") (pintype "output"))
    )
    (net (code "93") (name "Net-(U21-Q6)") (class "Default")
      (node (ref "R72") (pin "1") (pinfunction "1_1") (pintype "passive"))
      (node (ref "U21") (pin "6") (pinfunction "Q6_6") (pintype "output"))
    )
    (net (code "94") (name "Net-(U22-VDD)") (class "Default")
      (node (ref "C49") (pin "1") (pinfunction "1_1") (pintype "passive"))
      (node (ref "R77") (pin "1") (pinfunction "1_1") (pintype "passive"))
      (node (ref "U22") (pin "6") (pinfunction "VDD_6") (pintype "power_in"))
    )
    (net (code "95") (name "Net-(V1-B)") (class "Default")
      (node (ref "R53") (pin "2") (pinfunction "2_2") (pintype "passive"))
      (node (ref "R55") (pin "1") (pinfunction "1_1") (pintype "passive"))
      (node (ref "V1") (pin "1") (pinfunction "B_1") (pintype "passive"))
    )
    (net (code "96") (name "VCC_3V") (class "Default")
      (node (ref "C32") (pin "1") (pinfunction "1_1") (pintype "passive"))
      (node (ref "C33") (pin "1") (pinfunction "1_1") (pintype "passive"))
      (node (ref "C38") (pin "1") (pinfunction "1_1") (pintype "passive"))
      (node (ref "C39") (pin "1") (pinfunction "1_1") (pintype "passive"))
      (node (ref "C40") (pin "1") (pinfunction "1_1") (pintype "passive"))
      (node (ref "C41") (pin "1") (pinfunction "1_1") (pintype "passive"))
      (node (ref "C42") (pin "1") (pinfunction "1_1") (pintype "passive"))
      (node (ref "C43") (pin "1") (pinfunction "1_1") (pintype "passive"))
      (node (ref "C44") (pin "1") (pinfunction "1_1") (pintype "passive"))
      (node (ref "C45") (pin "1") (pinfunction "1_1") (pintype "passive"))
      (node (ref "C46") (pin "1") (pinfunction "1_1") (pintype "passive"))
      (node (ref "D19") (pin "2") (pintype "passive"))
      (node (ref "J9") (pin "3") (pinfunction "VCC3.3V_3") (pintype "passive"))
      (node (ref "R30") (pin "2") (pinfunction "2_2") (pintype "passive"))
      (node (ref "R43") (pin "2") (pinfunction "2_2") (pintype "passive"))
      (node (ref "R44") (pin "2") (pinfunction "2_2") (pintype "passive"))
      (node (ref "R47") (pin "2") (pinfunction "2_2") (pintype "passive"))
      (node (ref "R57") (pin "1") (pinfunction "1_1") (pintype "passive"))
      (node (ref "R71") (pin "2") (pinfunction "2_2") (pintype "passive"))
      (node (ref "R75") (pin "2") (pinfunction "2_2") (pintype "passive"))
      (node (ref "R76") (pin "2") (pinfunction "2_2") (pintype "passive"))
      (node (ref "R87") (pin "2") (pinfunction "2_2") (pintype "passive"))
      (node (ref "U15") (pin "2") (pinfunction "V+_2") (pintype "passive"))
      (node (ref "U16") (pin "2") (pinfunction "VCC_2") (pintype "power_in"))
      (node (ref "U17") (pin "14") (pinfunction "VCC_14") (pintype "passive"))
      (node (ref "U19") (pin "1") (pinfunction "VBAT_1") (pintype "power_in"))
      (node (ref "U19") (pin "13") (pinfunction "VDDA_13") (pintype "power_in"))
      (node (ref "U19") (pin "19") (pinfunction "VDD_4_19") (pintype "power_in"))
      (node (ref "U19") (pin "32") (pinfunction "VDD_1_32") (pintype "power_in"))
      (node (ref "U19") (pin "48") (pinfunction "VDD_2_48") (pintype "power_in"))
      (node (ref "U19") (pin "64") (pinfunction "VDD_3_64") (pintype "power_in"))
      (node (ref "U20") (pin "3") (pinfunction "~{WP}_3") (pintype "passive"))
      (node (ref "U20") (pin "7") (pinfunction "~{HOLD}_7") (pintype "passive"))
      (node (ref "U20") (pin "8") (pinfunction "VCC_8") (pintype "passive"))
      (node (ref "U21") (pin "10") (pinfunction "~{MR}_10") (pintype "input"))
      (node (ref "U21") (pin "16") (pinfunction "VCC_16") (pintype "power_in"))
    )
    (net (code "97") (name "VCC_4.1V") (class "Default")
      (node (ref "C29") (pin "1") (pinfunction "1_1") (pintype "passive"))
      (node (ref "C30") (pin "1") (pinfunction "1_1") (pintype "passive"))
      (node (ref "C31") (pin "1") (pinfunction "1_1") (pintype "passive"))
      (node (ref "EC6") (pin "1") (pinfunction "1_1") (pintype "passive"))
      (node (ref "M1") (pin "33") (pinfunction "VBAT_33") (pintype "passive"))
      (node (ref "M1") (pin "34") (pinfunction "VBAT_34") (pintype "passive"))
    )
    (net (code "98") (name "unconnected-(J9-NC-Pad1)") (class "Default")
      (node (ref "J9") (pin "1") (pinfunction "NC_1") (pintype "passive"))
    )
    (net (code "99") (name "unconnected-(M1-AGND-Pad1)") (class "Default")
      (node (ref "M1") (pin "1") (pinfunction "AGND_1") (pintype "passive+no_connect"))
    )
    (net (code "100") (name "unconnected-(M1-CTS-Pad23)") (class "Default")
      (node (ref "M1") (pin "23") (pinfunction "CTS_23") (pintype "passive+no_connect"))
    )
    (net (code "101") (name "unconnected-(M1-DBG_RXD-Pad14)") (class "Default")
      (node (ref "M1") (pin "14") (pinfunction "DBG_RXD_14") (pintype "passive"))
    )
    (net (code "102") (name "unconnected-(M1-DBG_TXD-Pad15)") (class "Default")
      (node (ref "M1") (pin "15") (pinfunction "DBG_TXD_15") (pintype "passive"))
    )
    (net (code "103") (name "unconnected-(M1-DCD-Pad25)") (class "Default")
      (node (ref "M1") (pin "25") (pinfunction "DCD_25") (pintype "passive+no_connect"))
    )
    (net (code "104") (name "unconnected-(M1-DTR-Pad20)") (class "Default")
      (node (ref "M1") (pin "20") (pinfunction "DTR_20") (pintype "passive+no_connect"))
    )
    (net (code "105") (name "unconnected-(M1-EMERG_OFF-Pad11)") (class "Default")
      (node (ref "M1") (pin "11") (pinfunction "EMERG_OFF_11") (pintype "passive+no_connect"))
    )
    (net (code "106") (name "unconnected-(M1-LOUDSPKN-Pad8)") (class "Default")
      (node (ref "M1") (pin "8") (pinfunction "LOUDSPKN_8") (pintype "passive+no_connect"))
    )
    (net (code "107") (name "unconnected-(M1-LOUDSPKP-Pad9)") (class "Default")
      (node (ref "M1") (pin "9") (pinfunction "LOUDSPKP_9") (pintype "passive+no_connect"))
    )
    (net (code "108") (name "unconnected-(M1-MIC1N-Pad5)") (class "Default")
      (node (ref "M1") (pin "5") (pinfunction "MIC1N_5") (pintype "passive+no_connect"))
    )
    (net (code "109") (name "unconnected-(M1-MIC1P-Pad4)") (class "Default")
      (node (ref "M1") (pin "4") (pinfunction "MIC1P_4") (pintype "passive+no_connect"))
    )
    (net (code "110") (name "unconnected-(M1-MIC2N-Pad3)") (class "Default")
      (node (ref "M1") (pin "3") (pinfunction "MIC2N_3") (pintype "passive+no_connect"))
    )
    (net (code "111") (name "unconnected-(M1-MIC2P-Pad2)") (class "Default")
      (node (ref "M1") (pin "2") (pinfunction "MIC2P_2") (pintype "passive+no_connect"))
    )
    (net (code "112") (name "unconnected-(M1-RESERVED-Pad16)") (class "Default")
      (node (ref "M1") (pin "16") (pinfunction "RESERVED_16") (pintype "passive"))
    )
    (net (code "113") (name "unconnected-(M1-RESERVED-Pad17)") (class "Default")
      (node (ref "M1") (pin "17") (pinfunction "RESERVED_17") (pintype "passive"))
    )
    (net (code "114") (name "unconnected-(M1-RESERVED-Pad18)") (class "Default")
      (node (ref "M1") (pin "18") (pinfunction "RESERVED_18") (pintype "passive"))
    )
    (net (code "115") (name "unconnected-(M1-RESERVED-Pad41)") (class "Default")
      (node (ref "M1") (pin "41") (pinfunction "RESERVED_41") (pintype "passive"))
    )
    (net (code "116") (name "unconnected-(M1-RESERVED-Pad42)") (class "Default")
      (node (ref "M1") (pin "42") (pinfunction "RESERVED_42") (pintype "passive"))
    )
    (net (code "117") (name "unconnected-(M1-RI-Pad26)") (class "Default")
      (node (ref "M1") (pin "26") (pinfunction "RI_26") (pintype "passive"))
    )
    (net (code "118") (name "unconnected-(M1-SPK1N-Pad6)") (class "Default")
      (node (ref "M1") (pin "6") (pinfunction "SPK1N_6") (pintype "passive+no_connect"))
    )
    (net (code "119") (name "unconnected-(M1-SPK1P-Pad7)") (class "Default")
      (node (ref "M1") (pin "7") (pinfunction "SPK1P_7") (pintype "passive+no_connect"))
    )
    (net (code "120") (name "unconnected-(M1-VDD_EXT-Pad19)") (class "Default")
      (node (ref "M1") (pin "19") (pinfunction "VDD_EXT_19") (pintype "passive"))
    )
    (net (code "121") (name "unconnected-(M1-VRTC-Pad32)") (class "Default")
      (node (ref "M1") (pin "32") (pinfunction "VRTC_32") (pintype "passive"))
    )
    (net (code "122") (name "unconnected-(S2-TLINK+-Pad7)") (class "Default")
      (node (ref "S2") (pin "7") (pinfunction "TLINK+_7") (pintype "passive"))
    )
    (net (code "123") (name "unconnected-(S2-TLINK--Pad8)") (class "Default")
      (node (ref "S2") (pin "8") (pinfunction "TLINK-_8") (pintype "passive"))
    )
    (net (code "124") (name "unconnected-(S2-VPP-Pad5)") (class "Default")
      (node (ref "S2") (pin "5") (pinfunction "VPP_5") (pintype "passive"))
    )
    (net (code "125") (name "unconnected-(U15-NO-Pad6)") (class "Default")
      (node (ref "U15") (pin "6") (pinfunction "NO_6") (pintype "passive"))
    )
    (net (code "126") (name "unconnected-(U17-Y4-Pad8)") (class "Default")
      (node (ref "U17") (pin "8") (pinfunction "Y4_8") (pintype "passive"))
    )
    (net (code "127") (name "unconnected-(U17-Y5-Pad10)") (class "Default")
      (node (ref "U17") (pin "10") (pinfunction "Y5_10") (pintype "passive"))
    )
    (net (code "128") (name "unconnected-(U17-Y6-Pad12)") (class "Default")
      (node (ref "U17") (pin "12") (pinfunction "Y6_12") (pintype "passive"))
    )
    (net (code "129") (name "unconnected-(U18-CH4-Pad6)") (class "Default")
      (node (ref "U18") (pin "6") (pinfunction "CH4_6") (pintype "passive"))
    )
    (net (code "130") (name "unconnected-(U19-PA0{slash}USART2_CTS{slash}ADC123_IN0-Pad14)") (class "Default")
      (node (ref "U19") (pin "14") (pinfunction "PA0/USART2_CTS/ADC123_IN0_14") (pintype "bidirectional"))
    )
    (net (code "131") (name "unconnected-(U19-PA8{slash}USART1_CK-Pad41)") (class "Default")
      (node (ref "U19") (pin "41") (pinfunction "PA8/USART1_CK_41") (pintype "bidirectional"))
    )
    (net (code "132") (name "unconnected-(U19-PA9{slash}USART1_TX-Pad42)") (class "Default")
      (node (ref "U19") (pin "42") (pinfunction "PA9/USART1_TX_42") (pintype "bidirectional"))
    )
    (net (code "133") (name "unconnected-(U19-PA10{slash}USART1_RX-Pad43)") (class "Default")
      (node (ref "U19") (pin "43") (pinfunction "PA10/USART1_RX_43") (pintype "bidirectional"))
    )
    (net (code "134") (name "unconnected-(U19-PB0{slash}ADC12_IN8-Pad26)") (class "Default")
      (node (ref "U19") (pin "26") (pinfunction "PB0/ADC12_IN8_26") (pintype "bidirectional"))
    )
    (net (code "135") (name "unconnected-(U19-PB13{slash}SPI2_SCK{slash}USART3_CTS-Pad34)") (class "Default")
      (node (ref "U19") (pin "34") (pinfunction "PB13/SPI2_SCK/USART3_CTS_34") (pintype "bidirectional"))
    )
    (net (code "136") (name "unconnected-(U19-PB14{slash}SPI2_MISO{slash}USART3_RTS-Pad35)") (class "Default")
      (node (ref "U19") (pin "35") (pinfunction "PB14/SPI2_MISO/USART3_RTS_35") (pintype "bidirectional"))
    )
    (net (code "137") (name "unconnected-(U19-PB15{slash}SPI2_MOSI-Pad36)") (class "Default")
      (node (ref "U19") (pin "36") (pinfunction "PB15/SPI2_MOSI_36") (pintype "bidirectional"))
    )
    (net (code "138") (name "unconnected-(U19-PC0{slash}ADC123_IN10-Pad8)") (class "Default")
      (node (ref "U19") (pin "8") (pinfunction "PC0/ADC123_IN10_8") (pintype "bidirectional"))
    )
    (net (code "139") (name "unconnected-(U19-PC13-TAMPER-RTC-Pad2)") (class "Default")
      (node (ref "U19") (pin "2") (pinfunction "PC13-TAMPER-RTC_2") (pintype "bidirectional"))
    )
    (net (code "140") (name "unconnected-(U19-PC14-OSC32_IN-Pad3)") (class "Default")
      (node (ref "U19") (pin "3") (pinfunction "PC14-OSC32_IN_3") (pintype "bidirectional"))
    )
    (net (code "141") (name "unconnected-(U19-PC15-OSC32_OUT-Pad4)") (class "Default")
      (node (ref "U19") (pin "4") (pinfunction "PC15-OSC32_OUT_4") (pintype "bidirectional"))
    )
    (net (code "142") (name "unconnected-(U21-Q7-Pad9)") (class "Default")
      (node (ref "U21") (pin "9") (pinfunction "Q7_9") (pintype "output"))
    )
    (net (code "143") (name "unconnected-(U22-FOE-Pad7)") (class "Default")
      (node (ref "U22") (pin "7") (pinfunction "FOE_7") (pintype "input+no_connect"))
    )
    (net (code "144") (name "unconnected-(U22-FOUT-Pad3)") (class "Default")
      (node (ref "U22") (pin "3") (pinfunction "FOUT_3") (pintype "output+no_connect"))
    )
    (net (code "145") (name "unconnected-(U22-~{INTA}-Pad10)") (class "Default")
      (node (ref "U22") (pin "10") (pinfunction "~{INTA}_10") (pintype "open_collector+no_connect"))
    )
    (net (code "146") (name "unconnected-(U22-~{INT}B-Pad12)") (class "Default")
      (node (ref "U22") (pin "12") (pinfunction "~{INT}B_12") (pintype "passive+no_connect"))
    )
  )
)
